# NixieClock.net
KiCad netlist of a schematic drawn in EAGLE
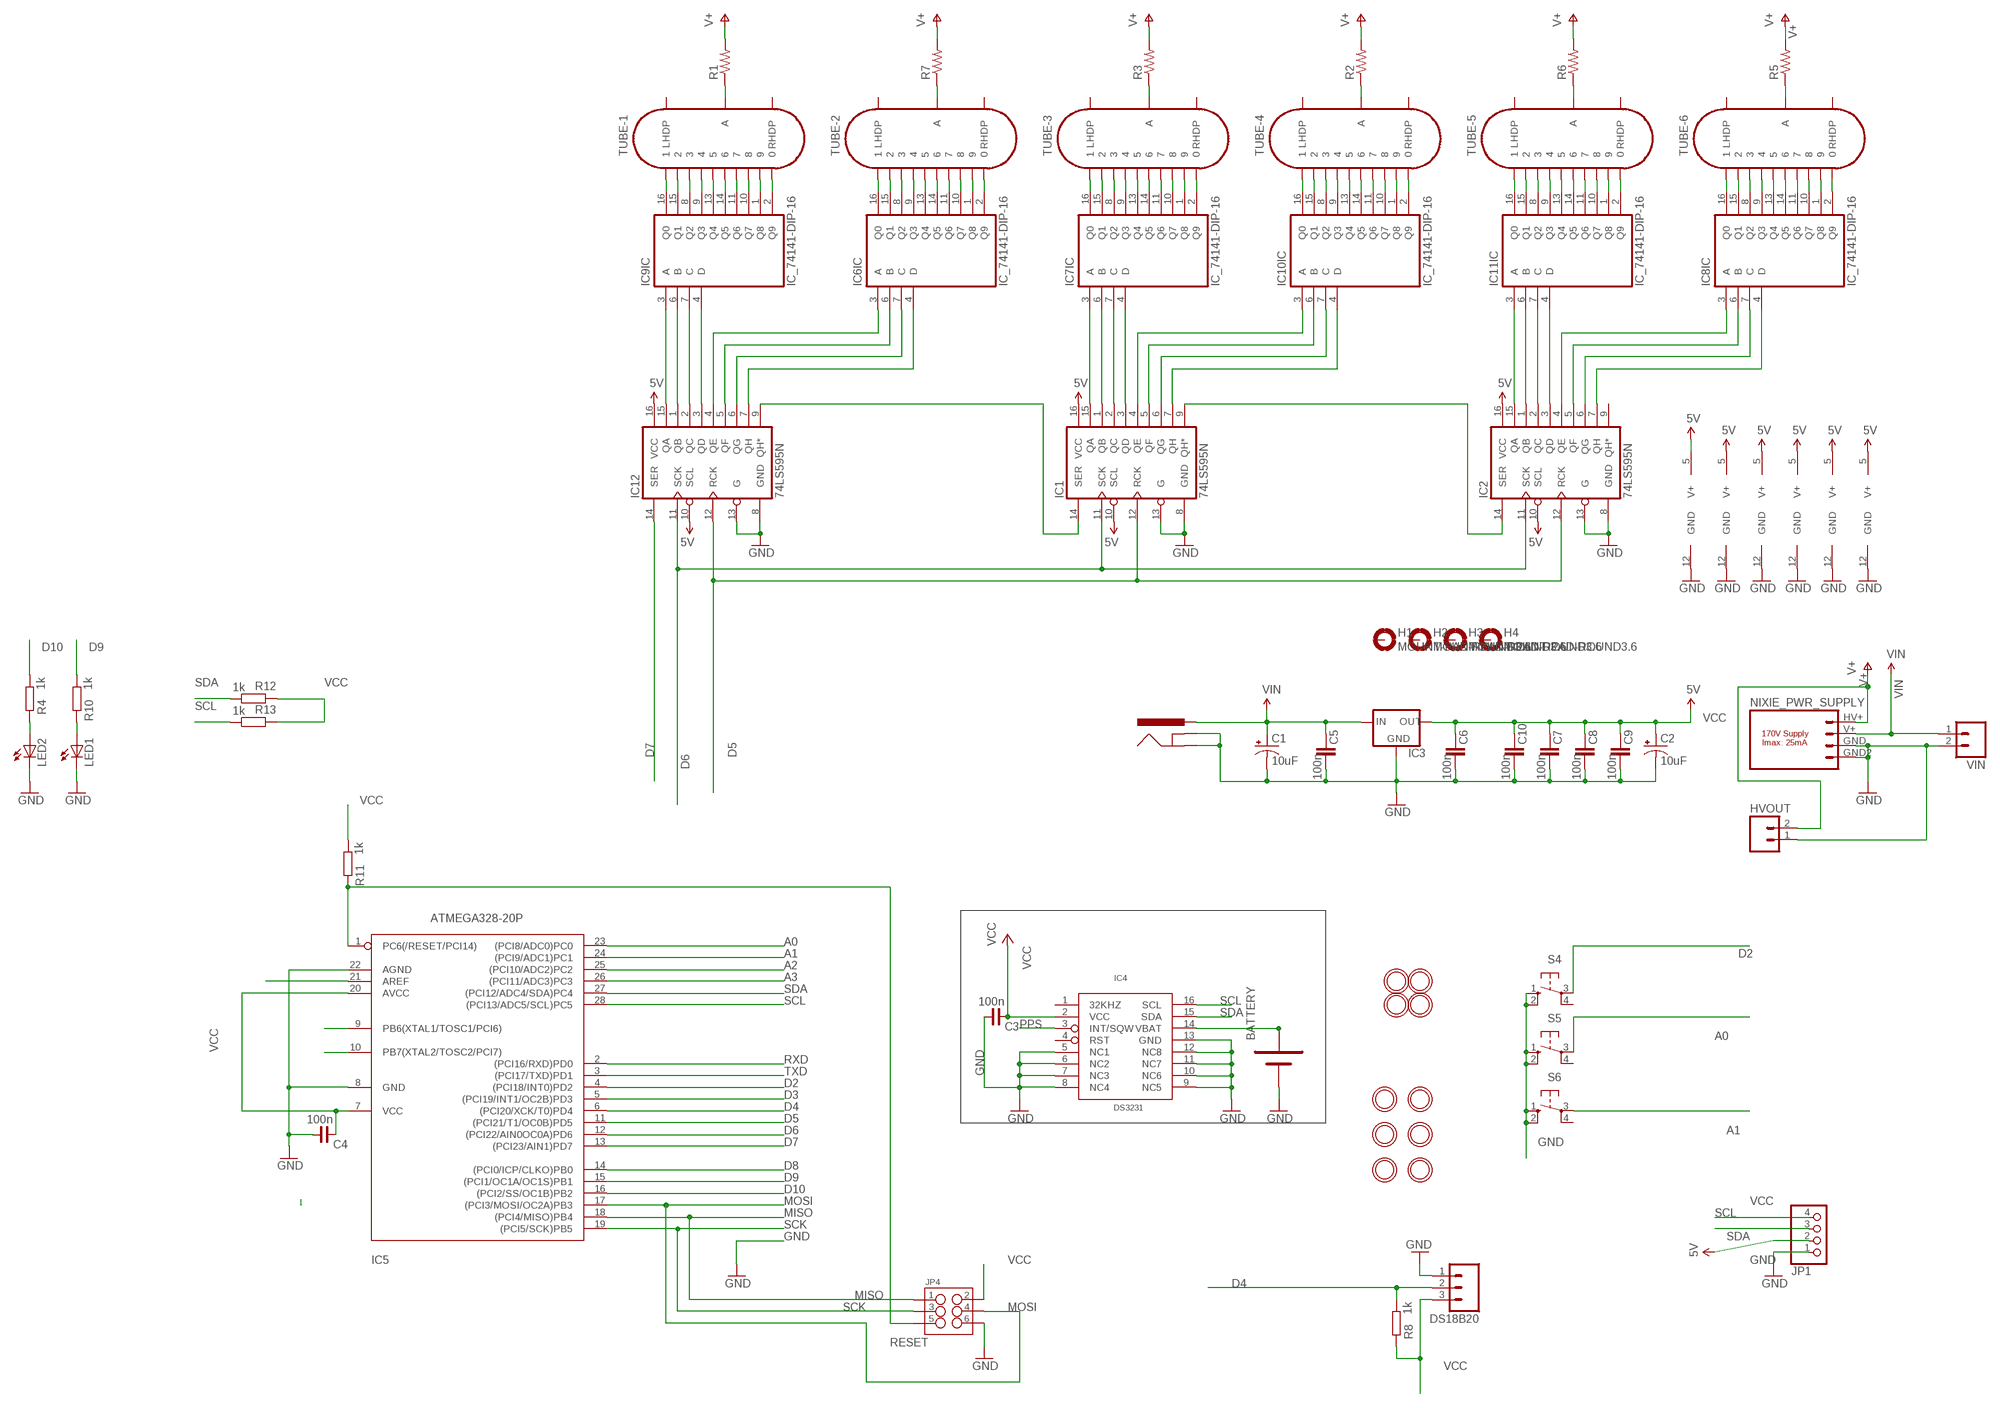
[diagram p0: schematic, sheet 1]

(export (version "E")
  (design (tool "Eeschema 10.0.6"))
  (components
    (comp (ref "BATTERY")
      (value "BATTERY-1XAA20MM")
      (footprint "eagle-import:BATTCOM_20MM_PTH")
      (libsource (lib "eagle-import") (part "BATTERY-1XAA20MM"))
    )
    (comp (ref "C1")
      (value "10uF")
      (footprint "eagle-import:CPOL-RADIAL-10UF-25V")
      (libsource (lib "eagle-import") (part "CAP_POLPTH2"))
    )
    (comp (ref "C2")
      (value "10uF")
      (footprint "eagle-import:CPOL-RADIAL-10UF-25V")
      (libsource (lib "eagle-import") (part "CAP_POLPTH2"))
    )
    (comp (ref "C3")
      (value "100n")
      (footprint "eagle-import:C0603")
      (libsource (lib "eagle-import") (part "C_0603"))
    )
    (comp (ref "C4")
      (value "100n")
      (footprint "eagle-import:C0603")
      (libsource (lib "eagle-import") (part "C_0603"))
    )
    (comp (ref "C5")
      (value "100n")
      (footprint "eagle-import:C050-025X075")
      (libsource (lib "eagle-import") (part "C-EU050-025X075"))
    )
    (comp (ref "C6")
      (value "100n")
      (footprint "eagle-import:C050-025X075")
      (libsource (lib "eagle-import") (part "C-EU050-025X075"))
    )
    (comp (ref "C7")
      (value "100n")
      (footprint "eagle-import:C050-025X075")
      (libsource (lib "eagle-import") (part "C-EU050-025X075"))
    )
    (comp (ref "C8")
      (value "100n")
      (footprint "eagle-import:C050-025X075")
      (libsource (lib "eagle-import") (part "C-EU050-025X075"))
    )
    (comp (ref "C9")
      (value "100n")
      (footprint "eagle-import:C050-025X075")
      (libsource (lib "eagle-import") (part "C-EU050-025X075"))
    )
    (comp (ref "C10")
      (value "100n")
      (footprint "eagle-import:C050-025X075")
      (libsource (lib "eagle-import") (part "C-EU050-025X075"))
    )
    (comp (ref "DS18B20")
      (value "DS18B20DS18B20")
      (footprint "eagle-import:DS18B20")
      (libsource (lib "eagle-import") (part "DS18B20DS18B20"))
    )
    (comp (ref "H1")
      (value "MOUNT-PAD-ROUND3.6")
      (footprint "eagle-import:3,6-PAD")
      (libsource (lib "eagle-import") (part "MOUNT-PAD-ROUND3.6"))
    )
    (comp (ref "H2")
      (value "MOUNT-PAD-ROUND3.6")
      (footprint "eagle-import:3,6-PAD")
      (libsource (lib "eagle-import") (part "MOUNT-PAD-ROUND3.6"))
    )
    (comp (ref "H3")
      (value "MOUNT-PAD-ROUND3.6")
      (footprint "eagle-import:3,6-PAD")
      (libsource (lib "eagle-import") (part "MOUNT-PAD-ROUND3.6"))
    )
    (comp (ref "H4")
      (value "MOUNT-PAD-ROUND3.6")
      (footprint "eagle-import:3,6-PAD")
      (libsource (lib "eagle-import") (part "MOUNT-PAD-ROUND3.6"))
    )
    (comp (ref "HVOUT")
      (value "M02PTH")
      (footprint "eagle-import:1X02")
      (libsource (lib "eagle-import") (part "M02PTH"))
    )
    (comp (ref "IC1")
      (value "74LS595N")
      (footprint "eagle-import:DIL16")
      (libsource (lib "eagle-import") (part "74595NLS"))
    )
    (comp (ref "IC2")
      (value "74LS595N")
      (footprint "eagle-import:DIL16")
      (libsource (lib "eagle-import") (part "74595NLS"))
    )
    (comp (ref "IC3")
      (value "V_REG_78XXSIDE")
      (footprint "eagle-import:78XXL")
      (libsource (lib "eagle-import") (part "V_REG_78XXSIDE"))
    )
    (comp (ref "IC4")
      (value "DS3231")
      (footprint "eagle-import:SO16W")
      (libsource (lib "eagle-import") (part "DS3231"))
    )
    (comp (ref "IC5")
      (value "ATMEGA328-20P")
      (footprint "eagle-import:DIL28-3")
      (libsource (lib "eagle-import") (part "ATMEGA168P-20"))
    )
    (comp (ref "IC6")
      (value "IC_74141-DIP-16")
      (footprint "eagle-import:DIL16")
      (libsource (lib "eagle-import") (part "IC_74141-DIP-16"))
    )
    (comp (ref "IC7")
      (value "IC_74141-DIP-16")
      (footprint "eagle-import:DIL16")
      (libsource (lib "eagle-import") (part "IC_74141-DIP-16"))
    )
    (comp (ref "IC8")
      (value "IC_74141-DIP-16")
      (footprint "eagle-import:DIL16")
      (libsource (lib "eagle-import") (part "IC_74141-DIP-16"))
    )
    (comp (ref "IC9")
      (value "IC_74141-DIP-16")
      (footprint "eagle-import:DIL16")
      (libsource (lib "eagle-import") (part "IC_74141-DIP-16"))
    )
    (comp (ref "IC10")
      (value "IC_74141-DIP-16")
      (footprint "eagle-import:DIL16")
      (libsource (lib "eagle-import") (part "IC_74141-DIP-16"))
    )
    (comp (ref "IC11")
      (value "IC_74141-DIP-16")
      (footprint "eagle-import:DIL16")
      (libsource (lib "eagle-import") (part "IC_74141-DIP-16"))
    )
    (comp (ref "IC12")
      (value "74LS595N")
      (footprint "eagle-import:DIL16")
      (libsource (lib "eagle-import") (part "74595NLS"))
    )
    (comp (ref "J1")
      (value "POWER_JACKPTH")
      (footprint "eagle-import:POWER_JACK_PTH")
      (libsource (lib "eagle-import") (part "POWER_JACKPTH"))
    )
    (comp (ref "JP1")
      (value "PINHD-1X4")
      (footprint "eagle-import:1X04")
      (libsource (lib "eagle-import") (part "PINHD-1X4"))
    )
    (comp (ref "JP4")
      (value "M03X2NO_SILK")
      (footprint "eagle-import:2X3-NS")
      (libsource (lib "eagle-import") (part "M03X2NO_SILK"))
    )
    (comp (ref "LED1")
      (value "LED3MM")
      (footprint "eagle-import:LED3MM")
      (libsource (lib "eagle-import") (part "LED3MM"))
    )
    (comp (ref "LED2")
      (value "LED3MM")
      (footprint "eagle-import:LED3MM")
      (libsource (lib "eagle-import") (part "LED3MM"))
    )
    (comp (ref "NIXIE_PWR_SUPPLY")
      (value "NIXIE_PWR_SUPPLYPTH")
      (footprint "eagle-import:NIXIE_PWR_SUPPLY")
      (libsource (lib "eagle-import") (part "NIXIE_PWR_SUPPLYPTH"))
    )
    (comp (ref "R1")
      (value "RESISTORPTH-1/4W")
      (footprint "eagle-import:AXIAL-0.4")
      (libsource (lib "eagle-import") (part "RESISTORPTH-1/4W"))
    )
    (comp (ref "R2")
      (value "RESISTORPTH-1/4W")
      (footprint "eagle-import:AXIAL-0.4")
      (libsource (lib "eagle-import") (part "RESISTORPTH-1/4W"))
    )
    (comp (ref "R3")
      (value "RESISTORPTH-1/4W")
      (footprint "eagle-import:AXIAL-0.4")
      (libsource (lib "eagle-import") (part "RESISTORPTH-1/4W"))
    )
    (comp (ref "R4")
      (value "1k")
      (footprint "eagle-import:0204_5")
      (libsource (lib "eagle-import") (part "R-EU_0204/5"))
    )
    (comp (ref "R5")
      (value "RESISTORPTH-1/4W")
      (footprint "eagle-import:AXIAL-0.4")
      (libsource (lib "eagle-import") (part "RESISTORPTH-1/4W"))
    )
    (comp (ref "R6")
      (value "RESISTORPTH-1/4W")
      (footprint "eagle-import:AXIAL-0.4")
      (libsource (lib "eagle-import") (part "RESISTORPTH-1/4W"))
    )
    (comp (ref "R7")
      (value "RESISTORPTH-1/4W")
      (footprint "eagle-import:AXIAL-0.4")
      (libsource (lib "eagle-import") (part "RESISTORPTH-1/4W"))
    )
    (comp (ref "R8")
      (value "1k")
      (footprint "eagle-import:0204_5")
      (libsource (lib "eagle-import") (part "R-EU_0204/5"))
    )
    (comp (ref "R10")
      (value "1k")
      (footprint "eagle-import:0204_5")
      (libsource (lib "eagle-import") (part "R-EU_0204/5"))
    )
    (comp (ref "R11")
      (value "1k")
      (footprint "eagle-import:0204_5")
      (libsource (lib "eagle-import") (part "R-EU_0204/5"))
    )
    (comp (ref "R12")
      (value "1k")
      (footprint "eagle-import:0204_5")
      (libsource (lib "eagle-import") (part "R-EU_0204/5"))
    )
    (comp (ref "R13")
      (value "1k")
      (footprint "eagle-import:0204_5")
      (libsource (lib "eagle-import") (part "R-EU_0204/5"))
    )
    (comp (ref "S4")
      (value "10-XX")
      (footprint "eagle-import:B3F-10XX")
      (fields (field (name "MPN") "B3F-1000"))
      (libsource (lib "eagle-import") (part "10-XX"))
    )
    (comp (ref "S5")
      (value "10-XX")
      (footprint "eagle-import:B3F-10XX")
      (fields (field (name "MPN") "B3F-1000"))
      (libsource (lib "eagle-import") (part "10-XX"))
    )
    (comp (ref "S6")
      (value "10-XX")
      (footprint "eagle-import:B3F-10XX")
      (fields (field (name "MPN") "B3F-1000"))
      (libsource (lib "eagle-import") (part "10-XX"))
    )
    (comp (ref "TUBE-1")
      (value "IN-14")
      (footprint "eagle-import:IN-14")
      (libsource (lib "eagle-import") (part "IN-14"))
    )
    (comp (ref "TUBE-2")
      (value "IN-14")
      (footprint "eagle-import:IN-14")
      (libsource (lib "eagle-import") (part "IN-14"))
    )
    (comp (ref "TUBE-3")
      (value "IN-14")
      (footprint "eagle-import:IN-14")
      (libsource (lib "eagle-import") (part "IN-14"))
    )
    (comp (ref "TUBE-4")
      (value "IN-14")
      (footprint "eagle-import:IN-14")
      (libsource (lib "eagle-import") (part "IN-14"))
    )
    (comp (ref "TUBE-5")
      (value "IN-14")
      (footprint "eagle-import:IN-14")
      (libsource (lib "eagle-import") (part "IN-14"))
    )
    (comp (ref "TUBE-6")
      (value "IN-14")
      (footprint "eagle-import:IN-14")
      (libsource (lib "eagle-import") (part "IN-14"))
    )
    (comp (ref "U$10")
      (value "MOUNTINGHOLE3.0THIN")
      (footprint "eagle-import:MOUNTINGHOLE_3.0_PLATEDTHIN")
      (libsource (lib "eagle-import") (part "MOUNTINGHOLE3.0THIN"))
    )
    (comp (ref "U$11")
      (value "MOUNTINGHOLE3.0THIN")
      (footprint "eagle-import:MOUNTINGHOLE_3.0_PLATEDTHIN")
      (libsource (lib "eagle-import") (part "MOUNTINGHOLE3.0THIN"))
    )
    (comp (ref "U$16")
      (value "MOUNTINGHOLE3.0THIN")
      (footprint "eagle-import:MOUNTINGHOLE_3.0_PLATEDTHIN")
      (libsource (lib "eagle-import") (part "MOUNTINGHOLE3.0THIN"))
    )
    (comp (ref "U$17")
      (value "MOUNTINGHOLE3.0THIN")
      (footprint "eagle-import:MOUNTINGHOLE_3.0_PLATEDTHIN")
      (libsource (lib "eagle-import") (part "MOUNTINGHOLE3.0THIN"))
    )
    (comp (ref "U$18")
      (value "MOUNTINGHOLE3.0THIN")
      (footprint "eagle-import:MOUNTINGHOLE_3.0_PLATEDTHIN")
      (libsource (lib "eagle-import") (part "MOUNTINGHOLE3.0THIN"))
    )
    (comp (ref "U$19")
      (value "MOUNTINGHOLE3.0THIN")
      (footprint "eagle-import:MOUNTINGHOLE_3.0_PLATEDTHIN")
      (libsource (lib "eagle-import") (part "MOUNTINGHOLE3.0THIN"))
    )
    (comp (ref "U$21")
      (value "MOUNTINGHOLE3.0THIN")
      (footprint "eagle-import:MOUNTINGHOLE_3.0_PLATEDTHIN")
      (libsource (lib "eagle-import") (part "MOUNTINGHOLE3.0THIN"))
    )
    (comp (ref "U$22")
      (value "MOUNTINGHOLE3.0THIN")
      (footprint "eagle-import:MOUNTINGHOLE_3.0_PLATEDTHIN")
      (libsource (lib "eagle-import") (part "MOUNTINGHOLE3.0THIN"))
    )
    (comp (ref "U$23")
      (value "MOUNTINGHOLE3.0THIN")
      (footprint "eagle-import:MOUNTINGHOLE_3.0_PLATEDTHIN")
      (libsource (lib "eagle-import") (part "MOUNTINGHOLE3.0THIN"))
    )
    (comp (ref "U$24")
      (value "MOUNTINGHOLE3.0THIN")
      (footprint "eagle-import:MOUNTINGHOLE_3.0_PLATEDTHIN")
      (libsource (lib "eagle-import") (part "MOUNTINGHOLE3.0THIN"))
    )
    (comp (ref "VIN")
      (value "M02PTH")
      (footprint "eagle-import:1X02")
      (libsource (lib "eagle-import") (part "M02PTH"))
    )
  )
  (nets
    (net (code "1") (name "/A0") (class "Default")
      (node (ref "IC5") (pin "23") (pinfunction "(PCI8/ADC0)PC0_23") (pintype "bidirectional"))
      (node (ref "S5") (pin "3") (pinfunction "P_3") (pintype "passive"))
    )
    (net (code "2") (name "/A1") (class "Default")
      (node (ref "IC5") (pin "24") (pinfunction "(PCI9/ADC1)PC1_24") (pintype "bidirectional"))
      (node (ref "S6") (pin "3") (pinfunction "P_3") (pintype "passive"))
    )
    (net (code "3") (name "/A2") (class "Default")
      (node (ref "IC5") (pin "25") (pinfunction "(PCI10/ADC2)PC2_25") (pintype "bidirectional"))
    )
    (net (code "4") (name "/A3") (class "Default")
      (node (ref "IC5") (pin "26") (pinfunction "(PCI11/ADC3)PC3_26") (pintype "bidirectional"))
    )
    (net (code "5") (name "/D2") (class "Default")
      (node (ref "IC5") (pin "4") (pinfunction "(PCI18/INT0)PD2_4") (pintype "bidirectional"))
      (node (ref "S4") (pin "3") (pinfunction "P_3") (pintype "passive"))
    )
    (net (code "6") (name "/D3") (class "Default")
      (node (ref "IC5") (pin "5") (pinfunction "(PCI19/INT1/OC2B)PD3_5") (pintype "bidirectional"))
    )
    (net (code "7") (name "/D4") (class "Default")
      (node (ref "DS18B20") (pin "2") (pinfunction "DS_2") (pintype "passive"))
      (node (ref "IC5") (pin "6") (pinfunction "(PCI20/XCK/T0)PD4_6") (pintype "bidirectional"))
      (node (ref "R8") (pin "1") (pinfunction "1_1") (pintype "passive"))
    )
    (net (code "8") (name "/D5") (class "Default")
      (node (ref "IC1") (pin "12") (pinfunction "RCK_12") (pintype "input"))
      (node (ref "IC12") (pin "12") (pinfunction "RCK_12") (pintype "input"))
      (node (ref "IC2") (pin "12") (pinfunction "RCK_12") (pintype "input"))
      (node (ref "IC5") (pin "11") (pinfunction "(PCI21/T1/OC0B)PD5_11") (pintype "bidirectional"))
    )
    (net (code "9") (name "/D6") (class "Default")
      (node (ref "IC1") (pin "11") (pinfunction "SCK_11") (pintype "input"))
      (node (ref "IC12") (pin "11") (pinfunction "SCK_11") (pintype "input"))
      (node (ref "IC2") (pin "11") (pinfunction "SCK_11") (pintype "input"))
      (node (ref "IC5") (pin "12") (pinfunction "(PCI22/AIN0OC0A)PD6_12") (pintype "bidirectional"))
    )
    (net (code "10") (name "/D7") (class "Default")
      (node (ref "IC12") (pin "14") (pinfunction "SER_14") (pintype "input"))
      (node (ref "IC5") (pin "13") (pinfunction "(PCI23/AIN1)PD7_13") (pintype "bidirectional"))
    )
    (net (code "11") (name "/D8") (class "Default")
      (node (ref "IC5") (pin "14") (pinfunction "(PCI0/ICP/CLKO)PB0_14") (pintype "bidirectional"))
    )
    (net (code "12") (name "/D9") (class "Default")
      (node (ref "IC5") (pin "15") (pinfunction "(PCI1/OC1A/OC1S)PB1_15") (pintype "bidirectional"))
      (node (ref "R10") (pin "1") (pinfunction "1_1") (pintype "passive"))
    )
    (net (code "13") (name "/D10") (class "Default")
      (node (ref "IC5") (pin "16") (pinfunction "(PCI2/SS/OC1B)PB2_16") (pintype "bidirectional"))
      (node (ref "R4") (pin "1") (pinfunction "1_1") (pintype "passive"))
    )
    (net (code "14") (name "/MISO") (class "Default")
      (node (ref "IC5") (pin "18") (pinfunction "(PCI4/MISO)PB4_18") (pintype "bidirectional"))
      (node (ref "JP4") (pin "1") (pinfunction "1_1") (pintype "bidirectional"))
    )
    (net (code "15") (name "/MOSI") (class "Default")
      (node (ref "IC5") (pin "17") (pinfunction "(PCI3/MOSI/OC2A)PB3_17") (pintype "bidirectional"))
      (node (ref "JP4") (pin "4") (pinfunction "4_4") (pintype "bidirectional"))
    )
    (net (code "16") (name "/PPS") (class "Default")
      (node (ref "IC4") (pin "3") (pinfunction "INT/SQW_3") (pintype "bidirectional"))
    )
    (net (code "17") (name "/RESET") (class "Default")
      (node (ref "IC5") (pin "1") (pinfunction "PC6(/RESET/PCI14)_1") (pintype "bidirectional"))
      (node (ref "JP4") (pin "5") (pinfunction "5_5") (pintype "bidirectional"))
      (node (ref "R11") (pin "2") (pinfunction "2_2") (pintype "passive"))
    )
    (net (code "18") (name "/RXD") (class "Default")
      (node (ref "IC5") (pin "2") (pinfunction "(PCI16/RXD)PD0_2") (pintype "bidirectional"))
    )
    (net (code "19") (name "/SCK") (class "Default")
      (node (ref "IC5") (pin "19") (pinfunction "(PCI5/SCK)PB5_19") (pintype "bidirectional"))
      (node (ref "JP4") (pin "3") (pinfunction "3_3") (pintype "bidirectional"))
    )
    (net (code "20") (name "/SCL") (class "Default")
      (node (ref "IC4") (pin "16") (pinfunction "SCL_16") (pintype "bidirectional"))
      (node (ref "IC5") (pin "28") (pinfunction "(PCI13/ADC5/SCL)PC5_28") (pintype "bidirectional"))
      (node (ref "JP1") (pin "4") (pinfunction "4_4") (pintype "passive"))
      (node (ref "R13") (pin "1") (pinfunction "1_1") (pintype "passive"))
    )
    (net (code "21") (name "/SDA") (class "Default")
      (node (ref "IC4") (pin "15") (pinfunction "SDA_15") (pintype "bidirectional"))
      (node (ref "IC5") (pin "27") (pinfunction "(PCI12/ADC4/SDA)PC4_27") (pintype "bidirectional"))
      (node (ref "JP1") (pin "3") (pinfunction "3_3") (pintype "passive"))
      (node (ref "R12") (pin "1") (pinfunction "1_1") (pintype "passive"))
    )
    (net (code "22") (name "/TXD") (class "Default")
      (node (ref "IC5") (pin "3") (pinfunction "(PCI17/TXD)PD1_3") (pintype "bidirectional"))
    )
    (net (code "23") (name "5V") (class "Default")
      (node (ref "C10") (pin "1") (pinfunction "1_1") (pintype "passive"))
      (node (ref "C2") (pin "1") (pinfunction "+_1") (pintype "passive"))
      (node (ref "C3") (pin "2") (pinfunction "2_2") (pintype "passive"))
      (node (ref "C4") (pin "2") (pinfunction "2_2") (pintype "passive"))
      (node (ref "C6") (pin "1") (pinfunction "1_1") (pintype "passive"))
      (node (ref "C7") (pin "1") (pinfunction "1_1") (pintype "passive"))
      (node (ref "C8") (pin "1") (pinfunction "1_1") (pintype "passive"))
      (node (ref "C9") (pin "1") (pinfunction "1_1") (pintype "passive"))
      (node (ref "DS18B20") (pin "3") (pinfunction "5V_3") (pintype "passive"))
      (node (ref "IC1") (pin "10") (pinfunction "SCL_10") (pintype "input"))
      (node (ref "IC1") (pin "16") (pinfunction "VCC_16") (pintype "power_in"))
      (node (ref "IC10") (pin "5") (pinfunction "V+_5") (pintype "power_in"))
      (node (ref "IC11") (pin "5") (pinfunction "V+_5") (pintype "power_in"))
      (node (ref "IC12") (pin "10") (pinfunction "SCL_10") (pintype "input"))
      (node (ref "IC12") (pin "16") (pinfunction "VCC_16") (pintype "power_in"))
      (node (ref "IC2") (pin "10") (pinfunction "SCL_10") (pintype "input"))
      (node (ref "IC2") (pin "16") (pinfunction "VCC_16") (pintype "power_in"))
      (node (ref "IC3") (pin "OUT") (pinfunction "OUT_OUT") (pintype "output"))
      (node (ref "IC4") (pin "2") (pinfunction "VCC_2") (pintype "power_in"))
      (node (ref "IC5") (pin "20") (pinfunction "AVCC_20") (pintype "bidirectional"))
      (node (ref "IC5") (pin "7") (pinfunction "VCC_7") (pintype "bidirectional"))
      (node (ref "IC6") (pin "5") (pinfunction "V+_5") (pintype "power_in"))
      (node (ref "IC7") (pin "5") (pinfunction "V+_5") (pintype "power_in"))
      (node (ref "IC8") (pin "5") (pinfunction "V+_5") (pintype "power_in"))
      (node (ref "IC9") (pin "5") (pinfunction "V+_5") (pintype "power_in"))
      (node (ref "JP1") (pin "2") (pinfunction "2_2") (pintype "passive"))
      (node (ref "JP4") (pin "2") (pinfunction "2_2") (pintype "bidirectional"))
      (node (ref "R11") (pin "1") (pinfunction "1_1") (pintype "passive"))
      (node (ref "R12") (pin "2") (pinfunction "2_2") (pintype "passive"))
      (node (ref "R13") (pin "2") (pinfunction "2_2") (pintype "passive"))
      (node (ref "R8") (pin "2") (pinfunction "2_2") (pintype "passive"))
    )
    (net (code "24") (name "GND") (class "Default")
      (node (ref "BATTERY") (pin "-") (pinfunction "-_-") (pintype "bidirectional"))
      (node (ref "C1") (pin "2") (pinfunction "-_2") (pintype "passive"))
      (node (ref "C10") (pin "2") (pinfunction "2_2") (pintype "passive"))
      (node (ref "C2") (pin "2") (pinfunction "-_2") (pintype "passive"))
      (node (ref "C3") (pin "1") (pinfunction "1_1") (pintype "passive"))
      (node (ref "C4") (pin "1") (pinfunction "1_1") (pintype "passive"))
      (node (ref "C5") (pin "2") (pinfunction "2_2") (pintype "passive"))
      (node (ref "C6") (pin "2") (pinfunction "2_2") (pintype "passive"))
      (node (ref "C7") (pin "2") (pinfunction "2_2") (pintype "passive"))
      (node (ref "C8") (pin "2") (pinfunction "2_2") (pintype "passive"))
      (node (ref "C9") (pin "2") (pinfunction "2_2") (pintype "passive"))
      (node (ref "DS18B20") (pin "1") (pinfunction "GND_1") (pintype "passive"))
      (node (ref "HVOUT") (pin "1") (pinfunction "1_1") (pintype "passive"))
      (node (ref "IC1") (pin "13") (pinfunction "G_13") (pintype "input"))
      (node (ref "IC1") (pin "8") (pinfunction "GND_8") (pintype "power_in"))
      (node (ref "IC10") (pin "12") (pinfunction "GND_12") (pintype "power_in"))
      (node (ref "IC11") (pin "12") (pinfunction "GND_12") (pintype "power_in"))
      (node (ref "IC12") (pin "13") (pinfunction "G_13") (pintype "input"))
      (node (ref "IC12") (pin "8") (pinfunction "GND_8") (pintype "power_in"))
      (node (ref "IC2") (pin "13") (pinfunction "G_13") (pintype "input"))
      (node (ref "IC2") (pin "8") (pinfunction "GND_8") (pintype "power_in"))
      (node (ref "IC3") (pin "GND") (pinfunction "GND_GND") (pintype "input"))
      (node (ref "IC4") (pin "10") (pinfunction "NC6_10") (pintype "bidirectional"))
      (node (ref "IC4") (pin "11") (pinfunction "NC7_11") (pintype "bidirectional"))
      (node (ref "IC4") (pin "12") (pinfunction "NC8_12") (pintype "bidirectional"))
      (node (ref "IC4") (pin "13") (pinfunction "GND_13") (pintype "power_in"))
      (node (ref "IC4") (pin "5") (pinfunction "NC1_5") (pintype "bidirectional"))
      (node (ref "IC4") (pin "6") (pinfunction "NC2_6") (pintype "bidirectional"))
      (node (ref "IC4") (pin "7") (pinfunction "NC3_7") (pintype "bidirectional"))
      (node (ref "IC4") (pin "8") (pinfunction "NC4_8") (pintype "bidirectional"))
      (node (ref "IC4") (pin "9") (pinfunction "NC5_9") (pintype "bidirectional"))
      (node (ref "IC5") (pin "22") (pinfunction "AGND_22") (pintype "bidirectional"))
      (node (ref "IC5") (pin "8") (pinfunction "GND_8") (pintype "bidirectional"))
      (node (ref "IC6") (pin "12") (pinfunction "GND_12") (pintype "power_in"))
      (node (ref "IC7") (pin "12") (pinfunction "GND_12") (pintype "power_in"))
      (node (ref "IC8") (pin "12") (pinfunction "GND_12") (pintype "power_in"))
      (node (ref "IC9") (pin "12") (pinfunction "GND_12") (pintype "power_in"))
      (node (ref "J1") (pin "GND") (pinfunction "GND_GND") (pintype "bidirectional"))
      (node (ref "J1") (pin "GNDBREAK") (pinfunction "GNDBREAK_GNDBREAK") (pintype "bidirectional"))
      (node (ref "JP1") (pin "1") (pinfunction "1_1") (pintype "passive"))
      (node (ref "JP4") (pin "6") (pinfunction "6_6") (pintype "bidirectional"))
      (node (ref "LED1") (pin "K") (pinfunction "C_K") (pintype "passive"))
      (node (ref "LED2") (pin "K") (pinfunction "C_K") (pintype "passive"))
      (node (ref "NIXIE_PWR_SUPPLY") (pin "GND") (pinfunction "4_GND") (pintype "passive"))
      (node (ref "NIXIE_PWR_SUPPLY") (pin "GND2") (pinfunction "1_GND2") (pintype "passive"))
      (node (ref "S4") (pin "1") (pinfunction "S_1") (pintype "passive"))
      (node (ref "S4") (pin "2") (pinfunction "S1_2") (pintype "passive"))
      (node (ref "S5") (pin "1") (pinfunction "S_1") (pintype "passive"))
      (node (ref "S5") (pin "2") (pinfunction "S1_2") (pintype "passive"))
      (node (ref "S6") (pin "1") (pinfunction "S_1") (pintype "passive"))
      (node (ref "S6") (pin "2") (pinfunction "S1_2") (pintype "passive"))
      (node (ref "VIN") (pin "2") (pinfunction "2_2") (pintype "passive"))
    )
    (net (code "25") (name "Net-(IC1-QA)") (class "Default")
      (node (ref "IC1") (pin "15") (pinfunction "QA_15") (pintype "tri_state"))
      (node (ref "IC7") (pin "3") (pinfunction "A_3") (pintype "input"))
    )
    (net (code "26") (name "Net-(IC1-QB)") (class "Default")
      (node (ref "IC1") (pin "1") (pinfunction "QB_1") (pintype "tri_state"))
      (node (ref "IC7") (pin "6") (pinfunction "B_6") (pintype "input"))
    )
    (net (code "27") (name "Net-(IC1-QC)") (class "Default")
      (node (ref "IC1") (pin "2") (pinfunction "QC_2") (pintype "tri_state"))
      (node (ref "IC7") (pin "7") (pinfunction "C_7") (pintype "input"))
    )
    (net (code "28") (name "Net-(IC1-QD)") (class "Default")
      (node (ref "IC1") (pin "3") (pinfunction "QD_3") (pintype "tri_state"))
      (node (ref "IC7") (pin "4") (pinfunction "D_4") (pintype "input"))
    )
    (net (code "29") (name "Net-(IC1-QE)") (class "Default")
      (node (ref "IC1") (pin "4") (pinfunction "QE_4") (pintype "tri_state"))
      (node (ref "IC10") (pin "3") (pinfunction "A_3") (pintype "input"))
    )
    (net (code "30") (name "Net-(IC1-QF)") (class "Default")
      (node (ref "IC1") (pin "5") (pinfunction "QF_5") (pintype "tri_state"))
      (node (ref "IC10") (pin "6") (pinfunction "B_6") (pintype "input"))
    )
    (net (code "31") (name "Net-(IC1-QG)") (class "Default")
      (node (ref "IC1") (pin "6") (pinfunction "QG_6") (pintype "tri_state"))
      (node (ref "IC10") (pin "7") (pinfunction "C_7") (pintype "input"))
    )
    (net (code "32") (name "Net-(IC1-QH)") (class "Default")
      (node (ref "IC1") (pin "7") (pinfunction "QH_7") (pintype "tri_state"))
      (node (ref "IC10") (pin "4") (pinfunction "D_4") (pintype "input"))
    )
    (net (code "33") (name "Net-(IC1-QH*)") (class "Default")
      (node (ref "IC1") (pin "9") (pinfunction "QH*_9") (pintype "tri_state"))
      (node (ref "IC2") (pin "14") (pinfunction "SER_14") (pintype "input"))
    )
    (net (code "34") (name "Net-(IC1-SER)") (class "Default")
      (node (ref "IC1") (pin "14") (pinfunction "SER_14") (pintype "input"))
      (node (ref "IC12") (pin "9") (pinfunction "QH*_9") (pintype "tri_state"))
    )
    (net (code "35") (name "Net-(IC2-QE)") (class "Default")
      (node (ref "IC2") (pin "4") (pinfunction "QE_4") (pintype "tri_state"))
      (node (ref "IC8") (pin "3") (pinfunction "A_3") (pintype "input"))
    )
    (net (code "36") (name "Net-(IC2-QF)") (class "Default")
      (node (ref "IC2") (pin "5") (pinfunction "QF_5") (pintype "tri_state"))
      (node (ref "IC8") (pin "6") (pinfunction "B_6") (pintype "input"))
    )
    (net (code "37") (name "Net-(IC2-QG)") (class "Default")
      (node (ref "IC2") (pin "6") (pinfunction "QG_6") (pintype "tri_state"))
      (node (ref "IC8") (pin "7") (pinfunction "C_7") (pintype "input"))
    )
    (net (code "38") (name "Net-(IC2-QH)") (class "Default")
      (node (ref "IC2") (pin "7") (pinfunction "QH_7") (pintype "tri_state"))
      (node (ref "IC8") (pin "4") (pinfunction "D_4") (pintype "input"))
    )
    (net (code "39") (name "Net-(IC4-VBAT)") (class "Default")
      (node (ref "BATTERY") (pin "+") (pinfunction "+_+") (pintype "bidirectional"))
      (node (ref "IC4") (pin "14") (pinfunction "VBAT_14") (pintype "bidirectional"))
    )
    (net (code "40") (name "Net-(IC6A-Q0)") (class "Default")
      (node (ref "IC6") (pin "16") (pinfunction "Q0_16") (pintype "output"))
      (node (ref "TUBE-2") (pin "1") (pinfunction "1_1") (pintype "bidirectional"))
    )
    (net (code "41") (name "Net-(IC6A-Q1)") (class "Default")
      (node (ref "IC6") (pin "15") (pinfunction "Q1_15") (pintype "output"))
      (node (ref "TUBE-2") (pin "2") (pinfunction "2_2") (pintype "bidirectional"))
    )
    (net (code "42") (name "Net-(IC6A-Q2)") (class "Default")
      (node (ref "IC6") (pin "8") (pinfunction "Q2_8") (pintype "output"))
      (node (ref "TUBE-2") (pin "3") (pinfunction "3_3") (pintype "bidirectional"))
    )
    (net (code "43") (name "Net-(IC6A-Q3)") (class "Default")
      (node (ref "IC6") (pin "9") (pinfunction "Q3_9") (pintype "output"))
      (node (ref "TUBE-2") (pin "4") (pinfunction "4_4") (pintype "bidirectional"))
    )
    (net (code "44") (name "Net-(IC6A-Q4)") (class "Default")
      (node (ref "IC6") (pin "13") (pinfunction "Q4_13") (pintype "output"))
      (node (ref "TUBE-2") (pin "5") (pinfunction "5_5") (pintype "bidirectional"))
    )
    (net (code "45") (name "Net-(IC6A-Q5)") (class "Default")
      (node (ref "IC6") (pin "14") (pinfunction "Q5_14") (pintype "output"))
      (node (ref "TUBE-2") (pin "6") (pinfunction "6_6") (pintype "bidirectional"))
    )
    (net (code "46") (name "Net-(IC6A-Q6)") (class "Default")
      (node (ref "IC6") (pin "11") (pinfunction "Q6_11") (pintype "output"))
      (node (ref "TUBE-2") (pin "7") (pinfunction "7_7") (pintype "bidirectional"))
    )
    (net (code "47") (name "Net-(IC6A-Q7)") (class "Default")
      (node (ref "IC6") (pin "10") (pinfunction "Q7_10") (pintype "output"))
      (node (ref "TUBE-2") (pin "8") (pinfunction "8_8") (pintype "bidirectional"))
    )
    (net (code "48") (name "Net-(IC6A-Q8)") (class "Default")
      (node (ref "IC6") (pin "1") (pinfunction "Q8_1") (pintype "output"))
      (node (ref "TUBE-2") (pin "9") (pinfunction "9_9") (pintype "bidirectional"))
    )
    (net (code "49") (name "Net-(IC6A-Q9)") (class "Default")
      (node (ref "IC6") (pin "2") (pinfunction "Q9_2") (pintype "output"))
      (node (ref "TUBE-2") (pin "0") (pinfunction "0_0") (pintype "bidirectional"))
    )
    (net (code "50") (name "Net-(IC7A-Q0)") (class "Default")
      (node (ref "IC7") (pin "16") (pinfunction "Q0_16") (pintype "output"))
      (node (ref "TUBE-3") (pin "1") (pinfunction "1_1") (pintype "bidirectional"))
    )
    (net (code "51") (name "Net-(IC7A-Q1)") (class "Default")
      (node (ref "IC7") (pin "15") (pinfunction "Q1_15") (pintype "output"))
      (node (ref "TUBE-3") (pin "2") (pinfunction "2_2") (pintype "bidirectional"))
    )
    (net (code "52") (name "Net-(IC7A-Q2)") (class "Default")
      (node (ref "IC7") (pin "8") (pinfunction "Q2_8") (pintype "output"))
      (node (ref "TUBE-3") (pin "3") (pinfunction "3_3") (pintype "bidirectional"))
    )
    (net (code "53") (name "Net-(IC7A-Q3)") (class "Default")
      (node (ref "IC7") (pin "9") (pinfunction "Q3_9") (pintype "output"))
      (node (ref "TUBE-3") (pin "4") (pinfunction "4_4") (pintype "bidirectional"))
    )
    (net (code "54") (name "Net-(IC7A-Q4)") (class "Default")
      (node (ref "IC7") (pin "13") (pinfunction "Q4_13") (pintype "output"))
      (node (ref "TUBE-3") (pin "5") (pinfunction "5_5") (pintype "bidirectional"))
    )
    (net (code "55") (name "Net-(IC7A-Q5)") (class "Default")
      (node (ref "IC7") (pin "14") (pinfunction "Q5_14") (pintype "output"))
      (node (ref "TUBE-3") (pin "6") (pinfunction "6_6") (pintype "bidirectional"))
    )
    (net (code "56") (name "Net-(IC7A-Q6)") (class "Default")
      (node (ref "IC7") (pin "11") (pinfunction "Q6_11") (pintype "output"))
      (node (ref "TUBE-3") (pin "7") (pinfunction "7_7") (pintype "bidirectional"))
    )
    (net (code "57") (name "Net-(IC7A-Q7)") (class "Default")
      (node (ref "IC7") (pin "10") (pinfunction "Q7_10") (pintype "output"))
      (node (ref "TUBE-3") (pin "8") (pinfunction "8_8") (pintype "bidirectional"))
    )
    (net (code "58") (name "Net-(IC7A-Q8)") (class "Default")
      (node (ref "IC7") (pin "1") (pinfunction "Q8_1") (pintype "output"))
      (node (ref "TUBE-3") (pin "9") (pinfunction "9_9") (pintype "bidirectional"))
    )
    (net (code "59") (name "Net-(IC7A-Q9)") (class "Default")
      (node (ref "IC7") (pin "2") (pinfunction "Q9_2") (pintype "output"))
      (node (ref "TUBE-3") (pin "0") (pinfunction "0_0") (pintype "bidirectional"))
    )
    (net (code "60") (name "Net-(IC8A-Q0)") (class "Default")
      (node (ref "IC8") (pin "16") (pinfunction "Q0_16") (pintype "output"))
      (node (ref "TUBE-6") (pin "1") (pinfunction "1_1") (pintype "bidirectional"))
    )
    (net (code "61") (name "Net-(IC8A-Q1)") (class "Default")
      (node (ref "IC8") (pin "15") (pinfunction "Q1_15") (pintype "output"))
      (node (ref "TUBE-6") (pin "2") (pinfunction "2_2") (pintype "bidirectional"))
    )
    (net (code "62") (name "Net-(IC8A-Q2)") (class "Default")
      (node (ref "IC8") (pin "8") (pinfunction "Q2_8") (pintype "output"))
      (node (ref "TUBE-6") (pin "3") (pinfunction "3_3") (pintype "bidirectional"))
    )
    (net (code "63") (name "Net-(IC8A-Q3)") (class "Default")
      (node (ref "IC8") (pin "9") (pinfunction "Q3_9") (pintype "output"))
      (node (ref "TUBE-6") (pin "4") (pinfunction "4_4") (pintype "bidirectional"))
    )
    (net (code "64") (name "Net-(IC8A-Q4)") (class "Default")
      (node (ref "IC8") (pin "13") (pinfunction "Q4_13") (pintype "output"))
      (node (ref "TUBE-6") (pin "5") (pinfunction "5_5") (pintype "bidirectional"))
    )
    (net (code "65") (name "Net-(IC8A-Q5)") (class "Default")
      (node (ref "IC8") (pin "14") (pinfunction "Q5_14") (pintype "output"))
      (node (ref "TUBE-6") (pin "6") (pinfunction "6_6") (pintype "bidirectional"))
    )
    (net (code "66") (name "Net-(IC8A-Q6)") (class "Default")
      (node (ref "IC8") (pin "11") (pinfunction "Q6_11") (pintype "output"))
      (node (ref "TUBE-6") (pin "7") (pinfunction "7_7") (pintype "bidirectional"))
    )
    (net (code "67") (name "Net-(IC8A-Q7)") (class "Default")
      (node (ref "IC8") (pin "10") (pinfunction "Q7_10") (pintype "output"))
      (node (ref "TUBE-6") (pin "8") (pinfunction "8_8") (pintype "bidirectional"))
    )
    (net (code "68") (name "Net-(IC8A-Q8)") (class "Default")
      (node (ref "IC8") (pin "1") (pinfunction "Q8_1") (pintype "output"))
      (node (ref "TUBE-6") (pin "9") (pinfunction "9_9") (pintype "bidirectional"))
    )
    (net (code "69") (name "Net-(IC8A-Q9)") (class "Default")
      (node (ref "IC8") (pin "2") (pinfunction "Q9_2") (pintype "output"))
      (node (ref "TUBE-6") (pin "0") (pinfunction "0_0") (pintype "bidirectional"))
    )
    (net (code "70") (name "Net-(IC9A-Q0)") (class "Default")
      (node (ref "IC9") (pin "16") (pinfunction "Q0_16") (pintype "output"))
      (node (ref "TUBE-1") (pin "1") (pinfunction "1_1") (pintype "bidirectional"))
    )
    (net (code "71") (name "Net-(IC9A-Q1)") (class "Default")
      (node (ref "IC9") (pin "15") (pinfunction "Q1_15") (pintype "output"))
      (node (ref "TUBE-1") (pin "2") (pinfunction "2_2") (pintype "bidirectional"))
    )
    (net (code "72") (name "Net-(IC9A-Q2)") (class "Default")
      (node (ref "IC9") (pin "8") (pinfunction "Q2_8") (pintype "output"))
      (node (ref "TUBE-1") (pin "3") (pinfunction "3_3") (pintype "bidirectional"))
    )
    (net (code "73") (name "Net-(IC9A-Q3)") (class "Default")
      (node (ref "IC9") (pin "9") (pinfunction "Q3_9") (pintype "output"))
      (node (ref "TUBE-1") (pin "4") (pinfunction "4_4") (pintype "bidirectional"))
    )
    (net (code "74") (name "Net-(IC9A-Q4)") (class "Default")
      (node (ref "IC9") (pin "13") (pinfunction "Q4_13") (pintype "output"))
      (node (ref "TUBE-1") (pin "5") (pinfunction "5_5") (pintype "bidirectional"))
    )
    (net (code "75") (name "Net-(IC9A-Q5)") (class "Default")
      (node (ref "IC9") (pin "14") (pinfunction "Q5_14") (pintype "output"))
      (node (ref "TUBE-1") (pin "6") (pinfunction "6_6") (pintype "bidirectional"))
    )
    (net (code "76") (name "Net-(IC9A-Q6)") (class "Default")
      (node (ref "IC9") (pin "11") (pinfunction "Q6_11") (pintype "output"))
      (node (ref "TUBE-1") (pin "7") (pinfunction "7_7") (pintype "bidirectional"))
    )
    (net (code "77") (name "Net-(IC9A-Q7)") (class "Default")
      (node (ref "IC9") (pin "10") (pinfunction "Q7_10") (pintype "output"))
      (node (ref "TUBE-1") (pin "8") (pinfunction "8_8") (pintype "bidirectional"))
    )
    (net (code "78") (name "Net-(IC9A-Q8)") (class "Default")
      (node (ref "IC9") (pin "1") (pinfunction "Q8_1") (pintype "output"))
      (node (ref "TUBE-1") (pin "9") (pinfunction "9_9") (pintype "bidirectional"))
    )
    (net (code "79") (name "Net-(IC9A-Q9)") (class "Default")
      (node (ref "IC9") (pin "2") (pinfunction "Q9_2") (pintype "output"))
      (node (ref "TUBE-1") (pin "0") (pinfunction "0_0") (pintype "bidirectional"))
    )
    (net (code "80") (name "Net-(IC10A-Q0)") (class "Default")
      (node (ref "IC10") (pin "16") (pinfunction "Q0_16") (pintype "output"))
      (node (ref "TUBE-4") (pin "1") (pinfunction "1_1") (pintype "bidirectional"))
    )
    (net (code "81") (name "Net-(IC10A-Q1)") (class "Default")
      (node (ref "IC10") (pin "15") (pinfunction "Q1_15") (pintype "output"))
      (node (ref "TUBE-4") (pin "2") (pinfunction "2_2") (pintype "bidirectional"))
    )
    (net (code "82") (name "Net-(IC10A-Q2)") (class "Default")
      (node (ref "IC10") (pin "8") (pinfunction "Q2_8") (pintype "output"))
      (node (ref "TUBE-4") (pin "3") (pinfunction "3_3") (pintype "bidirectional"))
    )
    (net (code "83") (name "Net-(IC10A-Q3)") (class "Default")
      (node (ref "IC10") (pin "9") (pinfunction "Q3_9") (pintype "output"))
      (node (ref "TUBE-4") (pin "4") (pinfunction "4_4") (pintype "bidirectional"))
    )
    (net (code "84") (name "Net-(IC10A-Q4)") (class "Default")
      (node (ref "IC10") (pin "13") (pinfunction "Q4_13") (pintype "output"))
      (node (ref "TUBE-4") (pin "5") (pinfunction "5_5") (pintype "bidirectional"))
    )
    (net (code "85") (name "Net-(IC10A-Q5)") (class "Default")
      (node (ref "IC10") (pin "14") (pinfunction "Q5_14") (pintype "output"))
      (node (ref "TUBE-4") (pin "6") (pinfunction "6_6") (pintype "bidirectional"))
    )
    (net (code "86") (name "Net-(IC10A-Q6)") (class "Default")
      (node (ref "IC10") (pin "11") (pinfunction "Q6_11") (pintype "output"))
      (node (ref "TUBE-4") (pin "7") (pinfunction "7_7") (pintype "bidirectional"))
    )
    (net (code "87") (name "Net-(IC10A-Q7)") (class "Default")
      (node (ref "IC10") (pin "10") (pinfunction "Q7_10") (pintype "output"))
      (node (ref "TUBE-4") (pin "8") (pinfunction "8_8") (pintype "bidirectional"))
    )
    (net (code "88") (name "Net-(IC10A-Q8)") (class "Default")
      (node (ref "IC10") (pin "1") (pinfunction "Q8_1") (pintype "output"))
      (node (ref "TUBE-4") (pin "9") (pinfunction "9_9") (pintype "bidirectional"))
    )
    (net (code "89") (name "Net-(IC10A-Q9)") (class "Default")
      (node (ref "IC10") (pin "2") (pinfunction "Q9_2") (pintype "output"))
      (node (ref "TUBE-4") (pin "0") (pinfunction "0_0") (pintype "bidirectional"))
    )
    (net (code "90") (name "Net-(IC11A-A)") (class "Default")
      (node (ref "IC11") (pin "3") (pinfunction "A_3") (pintype "input"))
      (node (ref "IC2") (pin "15") (pinfunction "QA_15") (pintype "tri_state"))
    )
    (net (code "91") (name "Net-(IC11A-B)") (class "Default")
      (node (ref "IC11") (pin "6") (pinfunction "B_6") (pintype "input"))
      (node (ref "IC2") (pin "1") (pinfunction "QB_1") (pintype "tri_state"))
    )
    (net (code "92") (name "Net-(IC11A-C)") (class "Default")
      (node (ref "IC11") (pin "7") (pinfunction "C_7") (pintype "input"))
      (node (ref "IC2") (pin "2") (pinfunction "QC_2") (pintype "tri_state"))
    )
    (net (code "93") (name "Net-(IC11A-D)") (class "Default")
      (node (ref "IC11") (pin "4") (pinfunction "D_4") (pintype "input"))
      (node (ref "IC2") (pin "3") (pinfunction "QD_3") (pintype "tri_state"))
    )
    (net (code "94") (name "Net-(IC11A-Q0)") (class "Default")
      (node (ref "IC11") (pin "16") (pinfunction "Q0_16") (pintype "output"))
      (node (ref "TUBE-5") (pin "1") (pinfunction "1_1") (pintype "bidirectional"))
    )
    (net (code "95") (name "Net-(IC11A-Q1)") (class "Default")
      (node (ref "IC11") (pin "15") (pinfunction "Q1_15") (pintype "output"))
      (node (ref "TUBE-5") (pin "2") (pinfunction "2_2") (pintype "bidirectional"))
    )
    (net (code "96") (name "Net-(IC11A-Q2)") (class "Default")
      (node (ref "IC11") (pin "8") (pinfunction "Q2_8") (pintype "output"))
      (node (ref "TUBE-5") (pin "3") (pinfunction "3_3") (pintype "bidirectional"))
    )
    (net (code "97") (name "Net-(IC11A-Q3)") (class "Default")
      (node (ref "IC11") (pin "9") (pinfunction "Q3_9") (pintype "output"))
      (node (ref "TUBE-5") (pin "4") (pinfunction "4_4") (pintype "bidirectional"))
    )
    (net (code "98") (name "Net-(IC11A-Q4)") (class "Default")
      (node (ref "IC11") (pin "13") (pinfunction "Q4_13") (pintype "output"))
      (node (ref "TUBE-5") (pin "5") (pinfunction "5_5") (pintype "bidirectional"))
    )
    (net (code "99") (name "Net-(IC11A-Q5)") (class "Default")
      (node (ref "IC11") (pin "14") (pinfunction "Q5_14") (pintype "output"))
      (node (ref "TUBE-5") (pin "6") (pinfunction "6_6") (pintype "bidirectional"))
    )
    (net (code "100") (name "Net-(IC11A-Q6)") (class "Default")
      (node (ref "IC11") (pin "11") (pinfunction "Q6_11") (pintype "output"))
      (node (ref "TUBE-5") (pin "7") (pinfunction "7_7") (pintype "bidirectional"))
    )
    (net (code "101") (name "Net-(IC11A-Q7)") (class "Default")
      (node (ref "IC11") (pin "10") (pinfunction "Q7_10") (pintype "output"))
      (node (ref "TUBE-5") (pin "8") (pinfunction "8_8") (pintype "bidirectional"))
    )
    (net (code "102") (name "Net-(IC11A-Q8)") (class "Default")
      (node (ref "IC11") (pin "1") (pinfunction "Q8_1") (pintype "output"))
      (node (ref "TUBE-5") (pin "9") (pinfunction "9_9") (pintype "bidirectional"))
    )
    (net (code "103") (name "Net-(IC11A-Q9)") (class "Default")
      (node (ref "IC11") (pin "2") (pinfunction "Q9_2") (pintype "output"))
      (node (ref "TUBE-5") (pin "0") (pinfunction "0_0") (pintype "bidirectional"))
    )
    (net (code "104") (name "Net-(IC12-QA)") (class "Default")
      (node (ref "IC12") (pin "15") (pinfunction "QA_15") (pintype "tri_state"))
      (node (ref "IC9") (pin "3") (pinfunction "A_3") (pintype "input"))
    )
    (net (code "105") (name "Net-(IC12-QB)") (class "Default")
      (node (ref "IC12") (pin "1") (pinfunction "QB_1") (pintype "tri_state"))
      (node (ref "IC9") (pin "6") (pinfunction "B_6") (pintype "input"))
    )
    (net (code "106") (name "Net-(IC12-QC)") (class "Default")
      (node (ref "IC12") (pin "2") (pinfunction "QC_2") (pintype "tri_state"))
      (node (ref "IC9") (pin "7") (pinfunction "C_7") (pintype "input"))
    )
    (net (code "107") (name "Net-(IC12-QD)") (class "Default")
      (node (ref "IC12") (pin "3") (pinfunction "QD_3") (pintype "tri_state"))
      (node (ref "IC9") (pin "4") (pinfunction "D_4") (pintype "input"))
    )
    (net (code "108") (name "Net-(IC12-QE)") (class "Default")
      (node (ref "IC12") (pin "4") (pinfunction "QE_4") (pintype "tri_state"))
      (node (ref "IC6") (pin "3") (pinfunction "A_3") (pintype "input"))
    )
    (net (code "109") (name "Net-(IC12-QF)") (class "Default")
      (node (ref "IC12") (pin "5") (pinfunction "QF_5") (pintype "tri_state"))
      (node (ref "IC6") (pin "6") (pinfunction "B_6") (pintype "input"))
    )
    (net (code "110") (name "Net-(IC12-QG)") (class "Default")
      (node (ref "IC12") (pin "6") (pinfunction "QG_6") (pintype "tri_state"))
      (node (ref "IC6") (pin "7") (pinfunction "C_7") (pintype "input"))
    )
    (net (code "111") (name "Net-(IC12-QH)") (class "Default")
      (node (ref "IC12") (pin "7") (pinfunction "QH_7") (pintype "tri_state"))
      (node (ref "IC6") (pin "4") (pinfunction "D_4") (pintype "input"))
    )
    (net (code "112") (name "Net-(LED1-PadA)") (class "Default")
      (node (ref "LED1") (pin "A") (pinfunction "A_A") (pintype "passive"))
      (node (ref "R10") (pin "2") (pinfunction "2_2") (pintype "passive"))
    )
    (net (code "113") (name "Net-(LED2-PadA)") (class "Default")
      (node (ref "LED2") (pin "A") (pinfunction "A_A") (pintype "passive"))
      (node (ref "R4") (pin "2") (pinfunction "2_2") (pintype "passive"))
    )
    (net (code "114") (name "Net-(R1-1)") (class "Default")
      (node (ref "R1") (pin "P$1") (pinfunction "1_P$1") (pintype "passive"))
      (node (ref "TUBE-1") (pin "A") (pinfunction "A_A") (pintype "bidirectional"))
    )
    (net (code "115") (name "Net-(R2-1)") (class "Default")
      (node (ref "R2") (pin "P$1") (pinfunction "1_P$1") (pintype "passive"))
      (node (ref "TUBE-4") (pin "A") (pinfunction "A_A") (pintype "bidirectional"))
    )
    (net (code "116") (name "Net-(R3-1)") (class "Default")
      (node (ref "R3") (pin "P$1") (pinfunction "1_P$1") (pintype "passive"))
      (node (ref "TUBE-3") (pin "A") (pinfunction "A_A") (pintype "bidirectional"))
    )
    (net (code "117") (name "Net-(R5-1)") (class "Default")
      (node (ref "R5") (pin "P$1") (pinfunction "1_P$1") (pintype "passive"))
      (node (ref "TUBE-6") (pin "A") (pinfunction "A_A") (pintype "bidirectional"))
    )
    (net (code "118") (name "Net-(R6-1)") (class "Default")
      (node (ref "R6") (pin "P$1") (pinfunction "1_P$1") (pintype "passive"))
      (node (ref "TUBE-5") (pin "A") (pinfunction "A_A") (pintype "bidirectional"))
    )
    (net (code "119") (name "Net-(R7-1)") (class "Default")
      (node (ref "R7") (pin "P$1") (pinfunction "1_P$1") (pintype "passive"))
      (node (ref "TUBE-2") (pin "A") (pinfunction "A_A") (pintype "bidirectional"))
    )
    (net (code "120") (name "V+") (class "Default")
      (node (ref "HVOUT") (pin "2") (pinfunction "2_2") (pintype "passive"))
      (node (ref "NIXIE_PWR_SUPPLY") (pin "HV+") (pinfunction "3_HV+") (pintype "passive"))
      (node (ref "R1") (pin "P$2") (pinfunction "2_P$2") (pintype "passive"))
      (node (ref "R2") (pin "P$2") (pinfunction "2_P$2") (pintype "passive"))
      (node (ref "R3") (pin "P$2") (pinfunction "2_P$2") (pintype "passive"))
      (node (ref "R5") (pin "P$2") (pinfunction "2_P$2") (pintype "passive"))
      (node (ref "R6") (pin "P$2") (pinfunction "2_P$2") (pintype "passive"))
      (node (ref "R7") (pin "P$2") (pinfunction "2_P$2") (pintype "passive"))
    )
    (net (code "121") (name "VIN") (class "Default")
      (node (ref "C1") (pin "1") (pinfunction "+_1") (pintype "passive"))
      (node (ref "C5") (pin "1") (pinfunction "1_1") (pintype "passive"))
      (node (ref "IC3") (pin "IN") (pinfunction "IN_IN") (pintype "input"))
      (node (ref "J1") (pin "PWR") (pinfunction "PWR_PWR") (pintype "bidirectional"))
      (node (ref "NIXIE_PWR_SUPPLY") (pin "V+") (pinfunction "2_V+") (pintype "passive"))
      (node (ref "VIN") (pin "1") (pinfunction "1_1") (pintype "passive"))
    )
    (net (code "122") (name "unconnected-(H1-MOUNT-PadB3,6)") (class "Default")
      (node (ref "H1") (pin "B3,6") (pinfunction "MOUNT_B3,6") (pintype "passive"))
    )
    (net (code "123") (name "unconnected-(H2-MOUNT-PadB3,6)") (class "Default")
      (node (ref "H2") (pin "B3,6") (pinfunction "MOUNT_B3,6") (pintype "passive"))
    )
    (net (code "124") (name "unconnected-(H3-MOUNT-PadB3,6)") (class "Default")
      (node (ref "H3") (pin "B3,6") (pinfunction "MOUNT_B3,6") (pintype "passive"))
    )
    (net (code "125") (name "unconnected-(H4-MOUNT-PadB3,6)") (class "Default")
      (node (ref "H4") (pin "B3,6") (pinfunction "MOUNT_B3,6") (pintype "passive"))
    )
    (net (code "126") (name "unconnected-(IC2-QH*-Pad9)") (class "Default")
      (node (ref "IC2") (pin "9") (pinfunction "QH*_9") (pintype "tri_state"))
    )
    (net (code "127") (name "unconnected-(IC4-32KHZ-Pad1)") (class "Default")
      (node (ref "IC4") (pin "1") (pinfunction "32KHZ_1") (pintype "bidirectional"))
    )
    (net (code "128") (name "unconnected-(IC4-RST-Pad4)") (class "Default")
      (node (ref "IC4") (pin "4") (pinfunction "RST_4") (pintype "bidirectional"))
    )
    (net (code "129") (name "unconnected-(IC5-AREF-Pad21)") (class "Default")
      (node (ref "IC5") (pin "21") (pinfunction "AREF_21") (pintype "bidirectional"))
    )
    (net (code "130") (name "unconnected-(IC5-PB6(XTAL1{slash}TOSC1{slash}PCI6)-Pad9)") (class "Default")
      (node (ref "IC5") (pin "9") (pinfunction "PB6(XTAL1/TOSC1/PCI6)_9") (pintype "bidirectional"))
    )
    (net (code "131") (name "unconnected-(IC5-PB7(XTAL2{slash}TOSC2{slash}PCI7)-Pad10)") (class "Default")
      (node (ref "IC5") (pin "10") (pinfunction "PB7(XTAL2/TOSC2/PCI7)_10") (pintype "bidirectional"))
    )
    (net (code "132") (name "unconnected-(S4-P1-Pad4)") (class "Default")
      (node (ref "S4") (pin "4") (pinfunction "P1_4") (pintype "passive"))
    )
    (net (code "133") (name "unconnected-(S5-P1-Pad4)") (class "Default")
      (node (ref "S5") (pin "4") (pinfunction "P1_4") (pintype "passive"))
    )
    (net (code "134") (name "unconnected-(S6-P1-Pad4)") (class "Default")
      (node (ref "S6") (pin "4") (pinfunction "P1_4") (pintype "passive"))
    )
    (net (code "135") (name "unconnected-(TUBE-1-PadLHDP)") (class "Default")
      (node (ref "TUBE-1") (pin "LHDP") (pinfunction "LHDP_LHDP") (pintype "bidirectional"))
    )
    (net (code "136") (name "unconnected-(TUBE-1-PadRHDP)") (class "Default")
      (node (ref "TUBE-1") (pin "RHDP") (pinfunction "RHDP_RHDP") (pintype "bidirectional"))
    )
    (net (code "137") (name "unconnected-(TUBE-2-PadLHDP)") (class "Default")
      (node (ref "TUBE-2") (pin "LHDP") (pinfunction "LHDP_LHDP") (pintype "bidirectional"))
    )
    (net (code "138") (name "unconnected-(TUBE-2-PadRHDP)") (class "Default")
      (node (ref "TUBE-2") (pin "RHDP") (pinfunction "RHDP_RHDP") (pintype "bidirectional"))
    )
    (net (code "139") (name "unconnected-(TUBE-3-PadLHDP)") (class "Default")
      (node (ref "TUBE-3") (pin "LHDP") (pinfunction "LHDP_LHDP") (pintype "bidirectional"))
    )
    (net (code "140") (name "unconnected-(TUBE-3-PadRHDP)") (class "Default")
      (node (ref "TUBE-3") (pin "RHDP") (pinfunction "RHDP_RHDP") (pintype "bidirectional"))
    )
    (net (code "141") (name "unconnected-(TUBE-4-PadLHDP)") (class "Default")
      (node (ref "TUBE-4") (pin "LHDP") (pinfunction "LHDP_LHDP") (pintype "bidirectional"))
    )
    (net (code "142") (name "unconnected-(TUBE-4-PadRHDP)") (class "Default")
      (node (ref "TUBE-4") (pin "RHDP") (pinfunction "RHDP_RHDP") (pintype "bidirectional"))
    )
    (net (code "143") (name "unconnected-(TUBE-5-PadLHDP)") (class "Default")
      (node (ref "TUBE-5") (pin "LHDP") (pinfunction "LHDP_LHDP") (pintype "bidirectional"))
    )
    (net (code "144") (name "unconnected-(TUBE-5-PadRHDP)") (class "Default")
      (node (ref "TUBE-5") (pin "RHDP") (pinfunction "RHDP_RHDP") (pintype "bidirectional"))
    )
    (net (code "145") (name "unconnected-(TUBE-6-PadLHDP)") (class "Default")
      (node (ref "TUBE-6") (pin "LHDP") (pinfunction "LHDP_LHDP") (pintype "bidirectional"))
    )
    (net (code "146") (name "unconnected-(TUBE-6-PadRHDP)") (class "Default")
      (node (ref "TUBE-6") (pin "RHDP") (pinfunction "RHDP_RHDP") (pintype "bidirectional"))
    )
  )
)
